# Sensors.net
KiCad netlist of a schematic drawn in EasyEDA
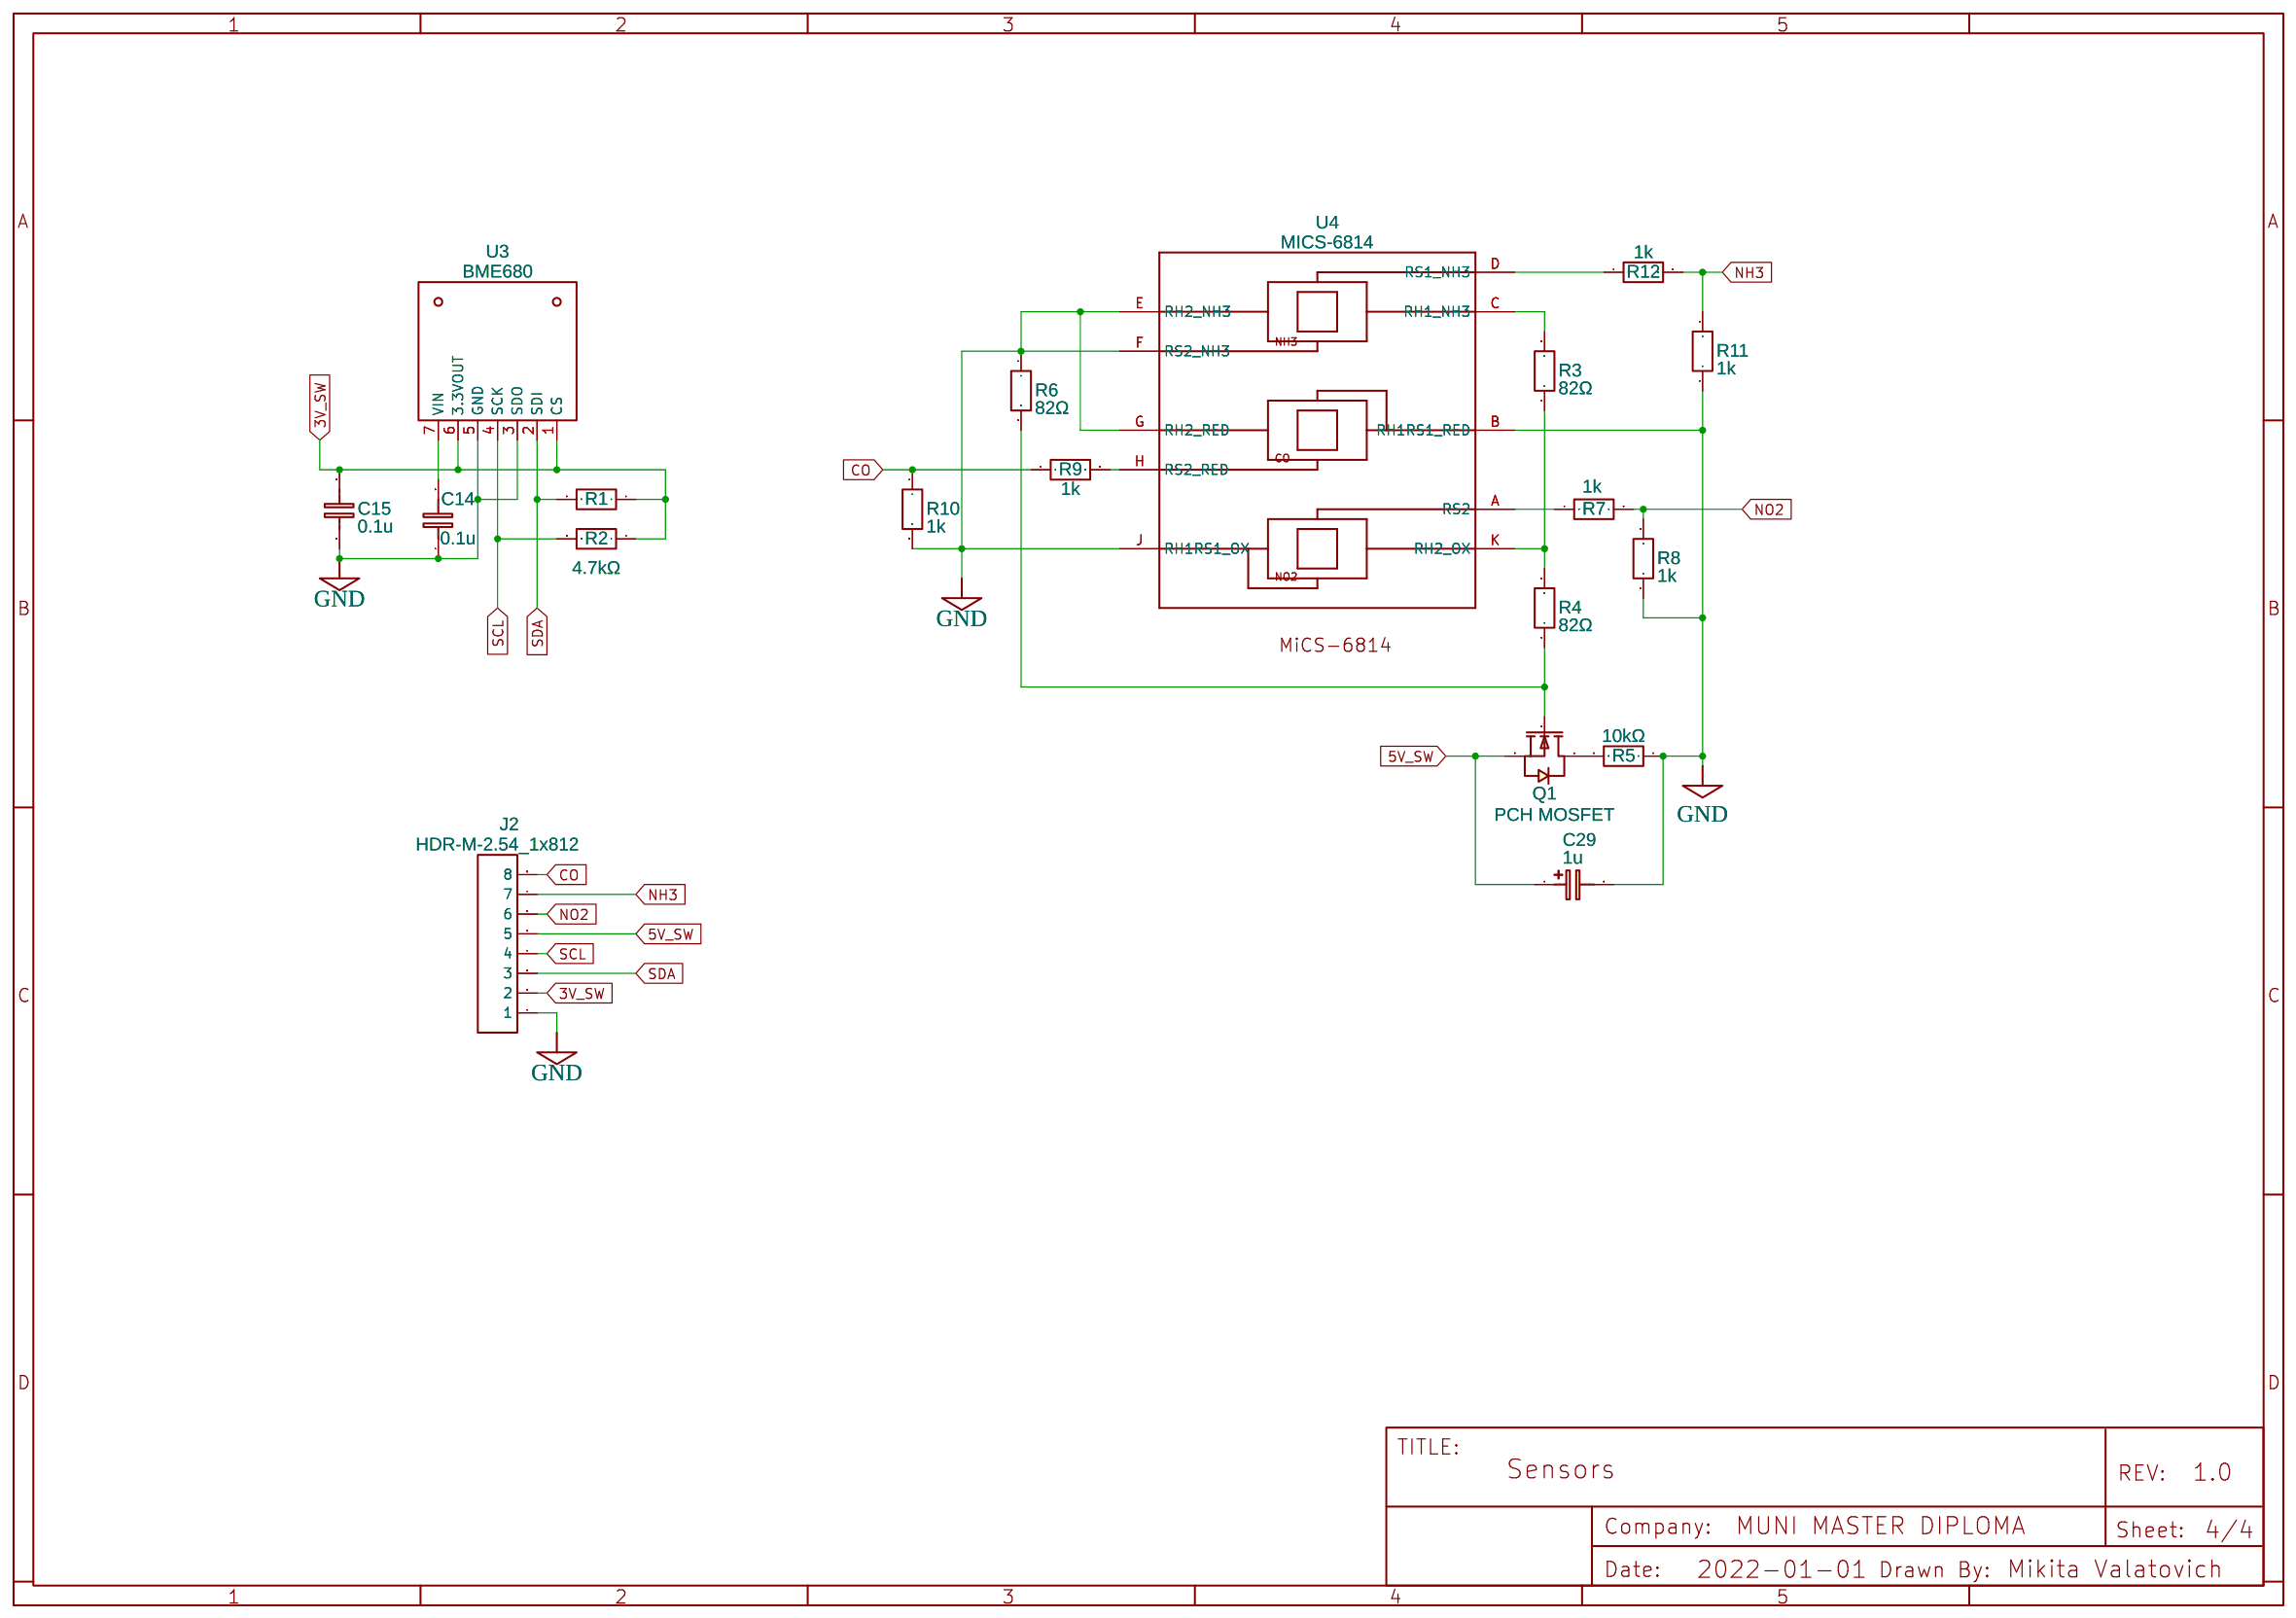
[diagram p0: schematic sheet]

(export (version "E")
  (design (tool "Eeschema 10.0.6"))
  (components
    (comp (ref "C14") (value "0.1u") (libsource (lib "") (part "C_0603_EU")))
    (comp (ref "C15") (value "0.1u") (libsource (lib "") (part "C_0603_EU")))
    (comp (ref "C29") (value "1u") (libsource (lib "") (part "C_Tan_SMD_A_EU")))
    (comp (ref "J2")
      (value "HDR-M-2.54_1x812")
      (fields (field (name "BOM_Supplier Part") "C190820"))
      (libsource (lib "") (part "HDR-M-2.54_1x812"))
    )
    (comp (ref "Q1")
      (value "PCH MOSFET")
      (fields (field (name "BOM_Manufacturer Part") "VB1240B") (field (name "BOM_Supplier Part") "C516873"))
      (libsource (lib "") (part "VB1240B"))
    )
    (comp (ref "R1")
      (value "4.7kΩ")
      (fields
        (field (name "BOM_Manufacturer Part") "TC0350D4701T5H")
        (field (name "BOM_Supplier Part") "C517493")
      )
      (libsource (lib "") (part "TC0350D4701T5H"))
    )
    (comp (ref "R2")
      (value "4.7kΩ")
      (fields
        (field (name "BOM_Manufacturer Part") "TC0350D4701T5H")
        (field (name "BOM_Supplier Part") "C517493")
      )
      (libsource (lib "") (part "TC0350D4701T5H"))
    )
    (comp (ref "R3")
      (value "82Ω")
      (fields
        (field (name "BOM_Manufacturer Part") "TCTR0603F47K0F3960T")
        (field (name "BOM_Supplier Part") "C525388")
      )
      (libsource (lib "") (part "TCTR0603F47K0F3960T_2"))
    )
    (comp (ref "R4")
      (value "82Ω")
      (fields
        (field (name "BOM_Manufacturer Part") "TCTR0603F47K0F3960T")
        (field (name "BOM_Supplier Part") "C525388")
      )
      (libsource (lib "") (part "TCTR0603F47K0F3960T_2"))
    )
    (comp (ref "R5")
      (value "10kΩ")
      (fields
        (field (name "BOM_Manufacturer Part") "TCTR0603F47K0F3960T")
        (field (name "BOM_Supplier Part") "C525388")
      )
      (libsource (lib "") (part "TCTR0603F47K0F3960T_1"))
    )
    (comp (ref "R6")
      (value "82Ω")
      (fields
        (field (name "BOM_Manufacturer Part") "TCTR0603F47K0F3960T")
        (field (name "BOM_Supplier Part") "C525388")
      )
      (libsource (lib "") (part "TCTR0603F47K0F3960T"))
    )
    (comp (ref "R7") (value "1k") (libsource (lib "") (part "R_0603_EU")))
    (comp (ref "R8") (value "1k") (libsource (lib "") (part "R_0603_EU_2")))
    (comp (ref "R9") (value "1k") (libsource (lib "") (part "R_0603_EU")))
    (comp (ref "R10") (value "1k") (libsource (lib "") (part "R_0603_EU_1")))
    (comp (ref "R11") (value "1k") (libsource (lib "") (part "R_0603_EU_1")))
    (comp (ref "R12") (value "1k") (libsource (lib "") (part "R_0603_EU")))
    (comp (ref "U3")
      (value "BME680")
      (fields (field (name "BOM_Supplier Part") "C125972"))
      (libsource (lib "") (part "BME680_ADAFRUIT"))
    )
    (comp (ref "U4") (value "MICS-6814") (libsource (lib "") (part "SENSOR-MICS-6814")))
  )
  (nets
    (net (code "1") (name "3V_SW") (class "Default")
      (node (ref "C15") (pin "2") (pinfunction "2_2") (pintype "unspecified"))
      (node (ref "J2") (pin "2") (pinfunction "2_2") (pintype "unspecified"))
      (node (ref "R1") (pin "1") (pinfunction "1_1") (pintype "unspecified"))
      (node (ref "R2") (pin "1") (pinfunction "1_1") (pintype "unspecified"))
      (node (ref "U3") (pin "1") (pinfunction "CS_1") (pintype "unspecified"))
      (node (ref "U3") (pin "6") (pinfunction "3.3VOUT_6") (pintype "unspecified"))
    )
    (net (code "2") (name "5V_SW") (class "Default")
      (node (ref "C29") (pin "1") (pinfunction "1_1") (pintype "unspecified"))
      (node (ref "J2") (pin "5") (pinfunction "5_5") (pintype "unspecified"))
      (node (ref "Q1") (pin "2") (pinfunction "S_2") (pintype "unspecified"))
    )
    (net (code "3") (name "CO") (class "Default")
      (node (ref "J2") (pin "8") (pinfunction "8_8") (pintype "unspecified"))
      (node (ref "R10") (pin "1") (pinfunction "1_1") (pintype "unspecified"))
      (node (ref "R9") (pin "1") (pinfunction "1_1") (pintype "unspecified"))
    )
    (net (code "4") (name "GND") (class "Default")
      (node (ref "C14") (pin "1") (pinfunction "1_1") (pintype "unspecified"))
      (node (ref "C15") (pin "1") (pinfunction "1_1") (pintype "unspecified"))
      (node (ref "C29") (pin "2") (pinfunction "2_2") (pintype "unspecified"))
      (node (ref "J2") (pin "1") (pinfunction "1_1") (pintype "unspecified"))
      (node (ref "R10") (pin "2") (pinfunction "2_2") (pintype "unspecified"))
      (node (ref "R11") (pin "2") (pinfunction "2_2") (pintype "unspecified"))
      (node (ref "R5") (pin "1") (pinfunction "1_1") (pintype "unspecified"))
      (node (ref "R6") (pin "1") (pinfunction "1_1") (pintype "unspecified"))
      (node (ref "R8") (pin "1") (pinfunction "1_1") (pintype "unspecified"))
      (node (ref "U3") (pin "3") (pinfunction "SDO_3") (pintype "unspecified"))
      (node (ref "U3") (pin "5") (pinfunction "GND_5") (pintype "unspecified"))
      (node (ref "U4") (pin "B") (pinfunction "RH1RS1_RED_B") (pintype "unspecified"))
      (node (ref "U4") (pin "E") (pinfunction "RH2_NH3_E") (pintype "unspecified"))
      (node (ref "U4") (pin "F") (pinfunction "RS2_NH3_F") (pintype "unspecified"))
      (node (ref "U4") (pin "G") (pinfunction "RH2_RED_G") (pintype "unspecified"))
      (node (ref "U4") (pin "J") (pinfunction "RH1RS1_OX_J") (pintype "unspecified"))
    )
    (net (code "5") (name "NH3") (class "Default")
      (node (ref "J2") (pin "7") (pinfunction "7_7") (pintype "unspecified"))
      (node (ref "R11") (pin "1") (pinfunction "1_1") (pintype "unspecified"))
      (node (ref "R12") (pin "2") (pinfunction "2_2") (pintype "unspecified"))
    )
    (net (code "6") (name "NO2") (class "Default")
      (node (ref "J2") (pin "6") (pinfunction "6_6") (pintype "unspecified"))
      (node (ref "R7") (pin "2") (pinfunction "2_2") (pintype "unspecified"))
      (node (ref "R8") (pin "2") (pinfunction "2_2") (pintype "unspecified"))
    )
    (net (code "7") (name "Net-(Q1-D)") (class "Default")
      (node (ref "Q1") (pin "3") (pinfunction "D_3") (pintype "unspecified"))
      (node (ref "R5") (pin "2") (pinfunction "2_2") (pintype "unspecified"))
    )
    (net (code "8") (name "Net-(Q1-G)") (class "Default")
      (node (ref "Q1") (pin "1") (pinfunction "G_1") (pintype "unspecified"))
      (node (ref "R4") (pin "1") (pinfunction "1_1") (pintype "unspecified"))
      (node (ref "R6") (pin "2") (pinfunction "2_2") (pintype "unspecified"))
    )
    (net (code "9") (name "Net-(U3-VIN)") (class "Default")
      (node (ref "C14") (pin "2") (pinfunction "2_2") (pintype "unspecified"))
      (node (ref "U3") (pin "7") (pinfunction "VIN_7") (pintype "unspecified"))
    )
    (net (code "10") (name "Net-(U4-RH1_NH3)") (class "Default")
      (node (ref "R3") (pin "2") (pinfunction "2_2") (pintype "unspecified"))
      (node (ref "U4") (pin "C") (pinfunction "RH1_NH3_C") (pintype "unspecified"))
    )
    (net (code "11") (name "Net-(U4-RH2_OX)") (class "Default")
      (node (ref "R3") (pin "1") (pinfunction "1_1") (pintype "unspecified"))
      (node (ref "R4") (pin "2") (pinfunction "2_2") (pintype "unspecified"))
      (node (ref "U4") (pin "K") (pinfunction "RH2_OX_K") (pintype "unspecified"))
    )
    (net (code "12") (name "Net-(U4-RS1_NH3)") (class "Default")
      (node (ref "R12") (pin "1") (pinfunction "1_1") (pintype "unspecified"))
      (node (ref "U4") (pin "D") (pinfunction "RS1_NH3_D") (pintype "unspecified"))
    )
    (net (code "13") (name "Net-(U4-RS2)") (class "Default")
      (node (ref "R7") (pin "1") (pinfunction "1_1") (pintype "unspecified"))
      (node (ref "U4") (pin "A") (pinfunction "RS2_A") (pintype "unspecified"))
    )
    (net (code "14") (name "Net-(U4-RS2_RED)") (class "Default")
      (node (ref "R9") (pin "2") (pinfunction "2_2") (pintype "unspecified"))
      (node (ref "U4") (pin "H") (pinfunction "RS2_RED_H") (pintype "unspecified"))
    )
    (net (code "15") (name "SCL") (class "Default")
      (node (ref "J2") (pin "4") (pinfunction "4_4") (pintype "unspecified"))
      (node (ref "R2") (pin "2") (pinfunction "2_2") (pintype "unspecified"))
      (node (ref "U3") (pin "4") (pinfunction "SCK_4") (pintype "unspecified"))
    )
    (net (code "16") (name "SDA") (class "Default")
      (node (ref "J2") (pin "3") (pinfunction "3_3") (pintype "unspecified"))
      (node (ref "R1") (pin "2") (pinfunction "2_2") (pintype "unspecified"))
      (node (ref "U3") (pin "2") (pinfunction "SDI_2") (pintype "unspecified"))
    )
  )
)
